# usbirtransceiver.net
KiCad netlist of a schematic drawn in EAGLE
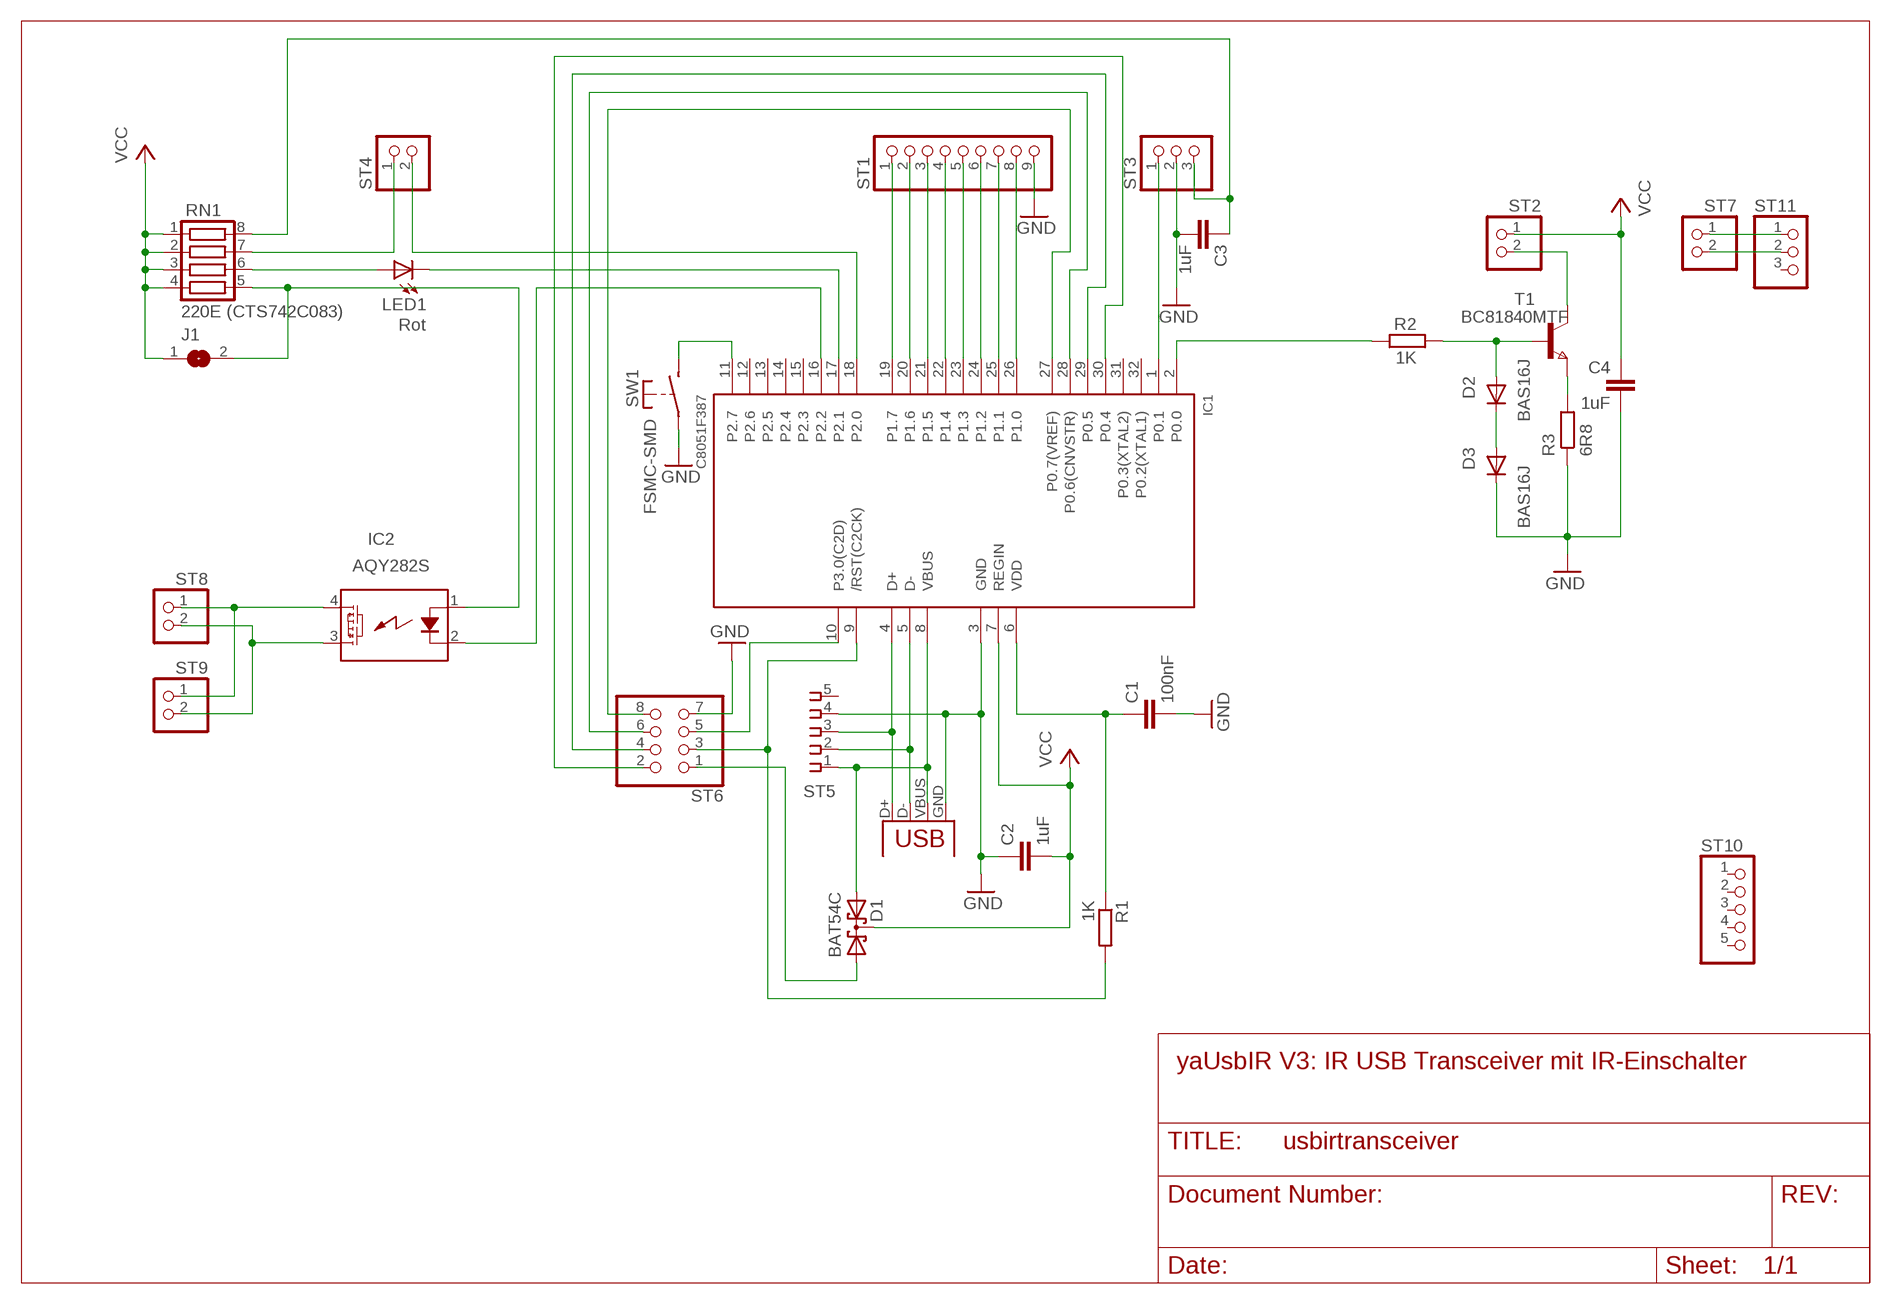
[diagram p0: schematic, sheet 1]

(export (version "E")
  (design (tool "Eeschema 10.0.6"))
  (components
    (comp (ref "C1")
      (value "100nF")
      (footprint "eagle-import:C0805")
      (libsource (lib "eagle-import") (part "C-EUC0805"))
    )
    (comp (ref "C2")
      (value "1uF")
      (footprint "eagle-import:C0805")
      (libsource (lib "eagle-import") (part "C-EUC0805"))
    )
    (comp (ref "C3")
      (value "1uF")
      (footprint "eagle-import:C0805")
      (libsource (lib "eagle-import") (part "C-EUC0805"))
    )
    (comp (ref "C4")
      (value "1uF")
      (footprint "eagle-import:C0805")
      (libsource (lib "eagle-import") (part "C-EUC0805"))
    )
    (comp (ref "D1")
      (value "BAT54C")
      (footprint "eagle-import:SOT23")
      (libsource (lib "eagle-import") (part "BAT54C"))
    )
    (comp (ref "D2")
      (value "BAS16J")
      (footprint "eagle-import:SOD323-R")
      (libsource (lib "eagle-import") (part "DIODE-SOD323-R"))
    )
    (comp (ref "D3")
      (value "BAS16J")
      (footprint "eagle-import:SOD323-R")
      (libsource (lib "eagle-import") (part "DIODE-SOD323-R"))
    )
    (comp (ref "IC1")
      (value "C8051F387")
      (footprint "eagle-import:TQFP32-08")
      (libsource (lib "eagle-import") (part "C8051F342"))
    )
    (comp (ref "IC2")
      (value "AQY282S")
      (footprint "eagle-import:SOP04")
      (libsource (lib "eagle-import") (part "AQYSOP22"))
    )
    (comp (ref "J1") (value "SJ") (footprint "eagle-import:SJ") (libsource (lib "eagle-import") (part "SJ")))
    (comp (ref "LED1")
      (value "Rot")
      (footprint "eagle-import:CHIP-LED0805")
      (libsource (lib "eagle-import") (part "LEDCHIP-LED0805"))
    )
    (comp (ref "R1")
      (value "1K")
      (footprint "eagle-import:R0805")
      (libsource (lib "eagle-import") (part "R-EU_R0805"))
    )
    (comp (ref "R2")
      (value "1K")
      (footprint "eagle-import:R0805")
      (libsource (lib "eagle-import") (part "R-EU_R0805"))
    )
    (comp (ref "R3")
      (value "6R8")
      (footprint "eagle-import:M1206")
      (libsource (lib "eagle-import") (part "R-EU_M1206"))
    )
    (comp (ref "RN1")
      (value "220E (CTS742C083)")
      (footprint "eagle-import:CTS742C083")
      (libsource (lib "eagle-import") (part "CTS742C083"))
    )
    (comp (ref "ST1")
      (value "PINHD-1X9")
      (footprint "eagle-import:1X09")
      (libsource (lib "eagle-import") (part "PINHD-1X9"))
    )
    (comp (ref "ST2")
      (value "PINHD-1X2")
      (footprint "eagle-import:1X02")
      (libsource (lib "eagle-import") (part "PINHD-1X2"))
    )
    (comp (ref "ST3")
      (value "PINHD-1X3")
      (footprint "eagle-import:1X03")
      (libsource (lib "eagle-import") (part "PINHD-1X3"))
    )
    (comp (ref "ST4")
      (value "PINHD-1X2")
      (footprint "eagle-import:1X02")
      (libsource (lib "eagle-import") (part "PINHD-1X2"))
    )
    (comp (ref "ST5")
      (value "CON5PINSMD2.54")
      (footprint "eagle-import:SMDTOP5")
      (libsource (lib "eagle-import") (part "CON5PINSMD2.54"))
    )
    (comp (ref "ST6")
      (value "PINHD-2X4")
      (footprint "eagle-import:2X04")
      (libsource (lib "eagle-import") (part "PINHD-2X4"))
    )
    (comp (ref "ST7")
      (value "PINHD-1X2")
      (footprint "eagle-import:1X02")
      (libsource (lib "eagle-import") (part "PINHD-1X2"))
    )
    (comp (ref "ST8")
      (value "PINHD-1X2")
      (footprint "eagle-import:1X02")
      (libsource (lib "eagle-import") (part "PINHD-1X2"))
    )
    (comp (ref "ST9")
      (value "PINHD-1X2")
      (footprint "eagle-import:1X02")
      (libsource (lib "eagle-import") (part "PINHD-1X2"))
    )
    (comp (ref "ST10")
      (value "PINHD-1X5_2.54-SMD-90°")
      (footprint "eagle-import:1X05SMD_90")
      (libsource (lib "eagle-import") (part "PINHD-1X5_2.54-SMD-90°"))
    )
    (comp (ref "ST11")
      (value "PINHD-1X3")
      (footprint "eagle-import:1X03")
      (libsource (lib "eagle-import") (part "PINHD-1X3"))
    )
    (comp (ref "ST12")
      (value "USB-MB-S")
      (footprint "eagle-import:USB-MB-S")
      (libsource (lib "eagle-import") (part "USB-MB-S"))
    )
    (comp (ref "SW1")
      (value "FSMC-SMD")
      (footprint "eagle-import:FSMC-SMD")
      (libsource (lib "eagle-import") (part "FSMC-SMD"))
    )
    (comp (ref "T1")
      (value "BC81840MTF")
      (footprint "eagle-import:SOT-23")
      (fields (field (name "MPN") "DSS20201L-7"))
      (libsource (lib "eagle-import") (part "NPNSOT23"))
    )
  )
  (nets
    (net (code "1") (name "GND") (class "Default")
      (node (ref "C1") (pin "2") (pinfunction "2_2") (pintype "passive"))
      (node (ref "C2") (pin "1") (pinfunction "1_1") (pintype "passive"))
      (node (ref "C3") (pin "2") (pinfunction "2_2") (pintype "passive"))
      (node (ref "C4") (pin "2") (pinfunction "2_2") (pintype "passive"))
      (node (ref "D3") (pin "C") (pinfunction "C_C") (pintype "passive"))
      (node (ref "IC1") (pin "3") (pinfunction "GND_3") (pintype "power_in"))
      (node (ref "R3") (pin "1") (pinfunction "1_1") (pintype "passive"))
      (node (ref "ST1") (pin "9") (pinfunction "9_9") (pintype "passive"))
      (node (ref "ST12") (pin "GND") (pinfunction "GND_GND") (pintype "bidirectional"))
      (node (ref "ST3") (pin "2") (pinfunction "2_2") (pintype "passive"))
      (node (ref "ST5") (pin "4") (pinfunction "4_4") (pintype "passive"))
      (node (ref "ST6") (pin "7") (pinfunction "7_7") (pintype "passive"))
      (node (ref "SW1") (pin "P$1") (pinfunction "P_P$1") (pintype "passive"))
    )
    (net (code "2") (name "Net-(C3-Pad1)") (class "Default")
      (node (ref "C3") (pin "1") (pinfunction "1_1") (pintype "passive"))
      (node (ref "RN1") (pin "8") (pinfunction "8_8") (pintype "passive"))
      (node (ref "ST3") (pin "3") (pinfunction "3_3") (pintype "passive"))
    )
    (net (code "3") (name "Net-(D1-A1)") (class "Default")
      (node (ref "D1") (pin "1") (pinfunction "A1_1") (pintype "passive"))
      (node (ref "ST6") (pin "1") (pinfunction "1_1") (pintype "passive"))
    )
    (net (code "4") (name "Net-(D1-A2)") (class "Default")
      (node (ref "D1") (pin "2") (pinfunction "A2_2") (pintype "passive"))
      (node (ref "IC1") (pin "8") (pinfunction "VBUS_8") (pintype "power_in"))
      (node (ref "ST12") (pin "VBUS") (pinfunction "VBUS_VBUS") (pintype "bidirectional"))
      (node (ref "ST5") (pin "1") (pinfunction "1_1") (pintype "passive"))
    )
    (net (code "5") (name "Net-(D2-PadC)") (class "Default")
      (node (ref "D2") (pin "C") (pinfunction "C_C") (pintype "passive"))
      (node (ref "D3") (pin "A") (pinfunction "A_A") (pintype "passive"))
    )
    (net (code "6") (name "Net-(IC1-D+)") (class "Default")
      (node (ref "IC1") (pin "4") (pinfunction "D+_4") (pintype "bidirectional"))
      (node (ref "ST12") (pin "D+") (pinfunction "D+_D+") (pintype "bidirectional"))
      (node (ref "ST5") (pin "3") (pinfunction "3_3") (pintype "passive"))
    )
    (net (code "7") (name "Net-(IC1-D-)") (class "Default")
      (node (ref "IC1") (pin "5") (pinfunction "D-_5") (pintype "bidirectional"))
      (node (ref "ST12") (pin "D-") (pinfunction "D-_D-") (pintype "bidirectional"))
      (node (ref "ST5") (pin "2") (pinfunction "2_2") (pintype "passive"))
    )
    (net (code "8") (name "Net-(IC1-P0.0)") (class "Default")
      (node (ref "IC1") (pin "2") (pinfunction "P0.0_2") (pintype "bidirectional"))
      (node (ref "R2") (pin "2") (pinfunction "2_2") (pintype "passive"))
    )
    (net (code "9") (name "Net-(IC1-P0.1)") (class "Default")
      (node (ref "IC1") (pin "1") (pinfunction "P0.1_1") (pintype "bidirectional"))
      (node (ref "ST3") (pin "1") (pinfunction "1_1") (pintype "passive"))
    )
    (net (code "10") (name "Net-(IC1-P0.4)") (class "Default")
      (node (ref "IC1") (pin "30") (pinfunction "P0.4_30") (pintype "bidirectional"))
      (node (ref "ST6") (pin "2") (pinfunction "2_2") (pintype "passive"))
    )
    (net (code "11") (name "Net-(IC1-P0.5)") (class "Default")
      (node (ref "IC1") (pin "29") (pinfunction "P0.5_29") (pintype "bidirectional"))
      (node (ref "ST6") (pin "4") (pinfunction "4_4") (pintype "passive"))
    )
    (net (code "12") (name "Net-(IC1-P0.6(CNVSTR))") (class "Default")
      (node (ref "IC1") (pin "28") (pinfunction "P0.6(CNVSTR)_28") (pintype "bidirectional"))
      (node (ref "ST6") (pin "6") (pinfunction "6_6") (pintype "passive"))
    )
    (net (code "13") (name "Net-(IC1-P0.7(VREF))") (class "Default")
      (node (ref "IC1") (pin "27") (pinfunction "P0.7(VREF)_27") (pintype "bidirectional"))
      (node (ref "ST6") (pin "8") (pinfunction "8_8") (pintype "passive"))
    )
    (net (code "14") (name "Net-(IC1-P1.0)") (class "Default")
      (node (ref "IC1") (pin "26") (pinfunction "P1.0_26") (pintype "bidirectional"))
      (node (ref "ST1") (pin "8") (pinfunction "8_8") (pintype "passive"))
    )
    (net (code "15") (name "Net-(IC1-P1.1)") (class "Default")
      (node (ref "IC1") (pin "25") (pinfunction "P1.1_25") (pintype "bidirectional"))
      (node (ref "ST1") (pin "7") (pinfunction "7_7") (pintype "passive"))
    )
    (net (code "16") (name "Net-(IC1-P1.2)") (class "Default")
      (node (ref "IC1") (pin "24") (pinfunction "P1.2_24") (pintype "bidirectional"))
      (node (ref "ST1") (pin "6") (pinfunction "6_6") (pintype "passive"))
    )
    (net (code "17") (name "Net-(IC1-P1.3)") (class "Default")
      (node (ref "IC1") (pin "23") (pinfunction "P1.3_23") (pintype "bidirectional"))
      (node (ref "ST1") (pin "5") (pinfunction "5_5") (pintype "passive"))
    )
    (net (code "18") (name "Net-(IC1-P1.4)") (class "Default")
      (node (ref "IC1") (pin "22") (pinfunction "P1.4_22") (pintype "bidirectional"))
      (node (ref "ST1") (pin "4") (pinfunction "4_4") (pintype "passive"))
    )
    (net (code "19") (name "Net-(IC1-P1.5)") (class "Default")
      (node (ref "IC1") (pin "21") (pinfunction "P1.5_21") (pintype "bidirectional"))
      (node (ref "ST1") (pin "3") (pinfunction "3_3") (pintype "passive"))
    )
    (net (code "20") (name "Net-(IC1-P1.6)") (class "Default")
      (node (ref "IC1") (pin "20") (pinfunction "P1.6_20") (pintype "bidirectional"))
      (node (ref "ST1") (pin "2") (pinfunction "2_2") (pintype "passive"))
    )
    (net (code "21") (name "Net-(IC1-P1.7)") (class "Default")
      (node (ref "IC1") (pin "19") (pinfunction "P1.7_19") (pintype "bidirectional"))
      (node (ref "ST1") (pin "1") (pinfunction "1_1") (pintype "passive"))
    )
    (net (code "22") (name "Net-(IC1-P2.0)") (class "Default")
      (node (ref "IC1") (pin "18") (pinfunction "P2.0_18") (pintype "bidirectional"))
      (node (ref "ST4") (pin "2") (pinfunction "2_2") (pintype "passive"))
    )
    (net (code "23") (name "Net-(IC1-P2.1)") (class "Default")
      (node (ref "IC1") (pin "17") (pinfunction "P2.1_17") (pintype "bidirectional"))
      (node (ref "LED1") (pin "C") (pinfunction "C_C") (pintype "passive"))
    )
    (net (code "24") (name "Net-(IC1-P2.2)") (class "Default")
      (node (ref "IC1") (pin "16") (pinfunction "P2.2_16") (pintype "bidirectional"))
      (node (ref "IC2") (pin "2") (pinfunction "K_2") (pintype "passive"))
    )
    (net (code "25") (name "Net-(IC1-P2.7)") (class "Default")
      (node (ref "IC1") (pin "11") (pinfunction "P2.7_11") (pintype "bidirectional"))
      (node (ref "SW1") (pin "P$2") (pinfunction "S_P$2") (pintype "passive"))
    )
    (net (code "26") (name "Net-(IC1-P3.0(C2D))") (class "Default")
      (node (ref "IC1") (pin "10") (pinfunction "P3.0(C2D)_10") (pintype "bidirectional"))
      (node (ref "ST6") (pin "5") (pinfunction "5_5") (pintype "passive"))
    )
    (net (code "27") (name "Net-(IC1-VDD)") (class "Default")
      (node (ref "C1") (pin "1") (pinfunction "1_1") (pintype "passive"))
      (node (ref "IC1") (pin "6") (pinfunction "VDD_6") (pintype "power_in"))
      (node (ref "R1") (pin "1") (pinfunction "1_1") (pintype "passive"))
    )
    (net (code "28") (name "Net-(IC1-{slash}RST(C2CK))") (class "Default")
      (node (ref "IC1") (pin "9") (pinfunction "/RST(C2CK)_9") (pintype "bidirectional"))
      (node (ref "R1") (pin "2") (pinfunction "2_2") (pintype "passive"))
      (node (ref "ST6") (pin "3") (pinfunction "3_3") (pintype "passive"))
    )
    (net (code "29") (name "Net-(IC2-A)") (class "Default")
      (node (ref "IC2") (pin "1") (pinfunction "A_1") (pintype "passive"))
      (node (ref "J1") (pin "2") (pinfunction "2_2") (pintype "passive"))
      (node (ref "RN1") (pin "5") (pinfunction "5_5") (pintype "passive"))
    )
    (net (code "30") (name "Net-(IC2-DS1)") (class "Default")
      (node (ref "IC2") (pin "4") (pinfunction "DS1_4") (pintype "passive"))
      (node (ref "ST8") (pin "1") (pinfunction "1_1") (pintype "passive"))
      (node (ref "ST9") (pin "1") (pinfunction "1_1") (pintype "passive"))
    )
    (net (code "31") (name "Net-(IC2-DS2)") (class "Default")
      (node (ref "IC2") (pin "3") (pinfunction "DS2_3") (pintype "passive"))
      (node (ref "ST8") (pin "2") (pinfunction "2_2") (pintype "passive"))
      (node (ref "ST9") (pin "2") (pinfunction "2_2") (pintype "passive"))
    )
    (net (code "32") (name "Net-(LED1-PadA)") (class "Default")
      (node (ref "LED1") (pin "A") (pinfunction "A_A") (pintype "passive"))
      (node (ref "RN1") (pin "6") (pinfunction "6_6") (pintype "passive"))
    )
    (net (code "33") (name "Net-(RN1-Pad7)") (class "Default")
      (node (ref "RN1") (pin "7") (pinfunction "7_7") (pintype "passive"))
      (node (ref "ST4") (pin "1") (pinfunction "1_1") (pintype "passive"))
    )
    (net (code "34") (name "Net-(ST11-Pad1)") (class "Default")
      (node (ref "ST11") (pin "1") (pinfunction "1_1") (pintype "passive"))
      (node (ref "ST7") (pin "1") (pinfunction "1_1") (pintype "passive"))
    )
    (net (code "35") (name "Net-(ST11-Pad2)") (class "Default")
      (node (ref "ST11") (pin "2") (pinfunction "2_2") (pintype "passive"))
      (node (ref "ST7") (pin "2") (pinfunction "2_2") (pintype "passive"))
    )
    (net (code "36") (name "Net-(T1-B)") (class "Default")
      (node (ref "D2") (pin "A") (pinfunction "A_A") (pintype "passive"))
      (node (ref "R2") (pin "1") (pinfunction "1_1") (pintype "passive"))
      (node (ref "T1") (pin "3") (pinfunction "B_3") (pintype "passive"))
    )
    (net (code "37") (name "Net-(T1-C)") (class "Default")
      (node (ref "ST2") (pin "2") (pinfunction "2_2") (pintype "passive"))
      (node (ref "T1") (pin "1") (pinfunction "C_1") (pintype "passive"))
    )
    (net (code "38") (name "Net-(T1-E)") (class "Default")
      (node (ref "R3") (pin "2") (pinfunction "2_2") (pintype "passive"))
      (node (ref "T1") (pin "2") (pinfunction "E_2") (pintype "passive"))
    )
    (net (code "39") (name "VCC") (class "Default")
      (node (ref "C2") (pin "2") (pinfunction "2_2") (pintype "passive"))
      (node (ref "C4") (pin "1") (pinfunction "1_1") (pintype "passive"))
      (node (ref "D1") (pin "3") (pinfunction "CC_3") (pintype "passive"))
      (node (ref "IC1") (pin "7") (pinfunction "REGIN_7") (pintype "power_in"))
      (node (ref "J1") (pin "1") (pinfunction "1_1") (pintype "passive"))
      (node (ref "RN1") (pin "1") (pinfunction "1_1") (pintype "passive"))
      (node (ref "RN1") (pin "2") (pinfunction "2_2") (pintype "passive"))
      (node (ref "RN1") (pin "3") (pinfunction "3_3") (pintype "passive"))
      (node (ref "RN1") (pin "4") (pinfunction "4_4") (pintype "passive"))
      (node (ref "ST2") (pin "1") (pinfunction "1_1") (pintype "passive"))
    )
    (net (code "40") (name "unconnected-(IC1-P0.2(XTAL1)-Pad32)") (class "Default")
      (node (ref "IC1") (pin "32") (pinfunction "P0.2(XTAL1)_32") (pintype "bidirectional"))
    )
    (net (code "41") (name "unconnected-(IC1-P0.3(XTAL2)-Pad31)") (class "Default")
      (node (ref "IC1") (pin "31") (pinfunction "P0.3(XTAL2)_31") (pintype "bidirectional"))
    )
    (net (code "42") (name "unconnected-(IC1-P2.3-Pad15)") (class "Default")
      (node (ref "IC1") (pin "15") (pinfunction "P2.3_15") (pintype "bidirectional"))
    )
    (net (code "43") (name "unconnected-(IC1-P2.4-Pad14)") (class "Default")
      (node (ref "IC1") (pin "14") (pinfunction "P2.4_14") (pintype "bidirectional"))
    )
    (net (code "44") (name "unconnected-(IC1-P2.5-Pad13)") (class "Default")
      (node (ref "IC1") (pin "13") (pinfunction "P2.5_13") (pintype "bidirectional"))
    )
    (net (code "45") (name "unconnected-(IC1-P2.6-Pad12)") (class "Default")
      (node (ref "IC1") (pin "12") (pinfunction "P2.6_12") (pintype "bidirectional"))
    )
    (net (code "46") (name "unconnected-(ST5-Pad5)") (class "Default")
      (node (ref "ST5") (pin "5") (pinfunction "5_5") (pintype "passive"))
    )
    (net (code "47") (name "unconnected-(ST10-Pad1)") (class "Default")
      (node (ref "ST10") (pin "1") (pinfunction "1_1") (pintype "passive"))
    )
    (net (code "48") (name "unconnected-(ST10-Pad2)") (class "Default")
      (node (ref "ST10") (pin "2") (pinfunction "2_2") (pintype "passive"))
    )
    (net (code "49") (name "unconnected-(ST10-Pad3)") (class "Default")
      (node (ref "ST10") (pin "3") (pinfunction "3_3") (pintype "passive"))
    )
    (net (code "50") (name "unconnected-(ST10-Pad4)") (class "Default")
      (node (ref "ST10") (pin "4") (pinfunction "4_4") (pintype "passive"))
    )
    (net (code "51") (name "unconnected-(ST10-Pad5)") (class "Default")
      (node (ref "ST10") (pin "5") (pinfunction "5_5") (pintype "passive"))
    )
    (net (code "52") (name "unconnected-(ST11-Pad3)") (class "Default")
      (node (ref "ST11") (pin "3") (pinfunction "3_3") (pintype "passive"))
    )
  )
)
